# termopar.net
KiCad netlist of a schematic drawn in EAGLE
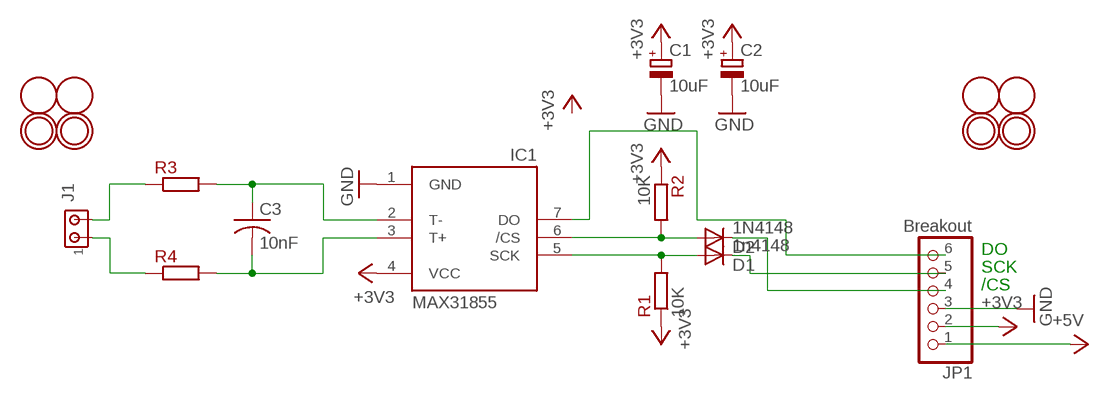
[diagram p0: schematic, sheet 1]

(export (version "E")
  (design (tool "Eeschema 10.0.6"))
  (components
    (comp (ref "C1")
      (value "10uF")
      (footprint "eagle-import:E3,5-8")
      (libsource (lib "eagle-import") (part "CPOL-EUE3.5-8"))
    )
    (comp (ref "C2")
      (value "10uF")
      (footprint "eagle-import:E3,5-8")
      (libsource (lib "eagle-import") (part "CPOL-EUE3.5-8"))
    )
    (comp (ref "C3")
      (value "10nF")
      (footprint "eagle-import:C050-030X075")
      (libsource (lib "eagle-import") (part "C-US050-030X075"))
    )
    (comp (ref "D1")
      (value "1n4148")
      (footprint "eagle-import:DO35-7")
      (libsource (lib "eagle-import") (part "1N4148DO35-7"))
    )
    (comp (ref "D2")
      (value "1N4148")
      (footprint "eagle-import:DO35-7")
      (libsource (lib "eagle-import") (part "1N4148DO35-7"))
    )
    (comp (ref "IC1")
      (value "MAX31855")
      (footprint "eagle-import:SO08")
      (libsource (lib "eagle-import") (part "MAX6675"))
    )
    (comp (ref "J1")
      (value "MTA02-156")
      (footprint "eagle-import:1X2MTA")
      (libsource (lib "eagle-import") (part "MTA02-156"))
    )
    (comp (ref "JP1")
      (value "Breakout")
      (footprint "eagle-import:1X06_ROUND_76")
      (libsource (lib "eagle-import") (part "HEADER-1X676MIL"))
    )
    (comp (ref "R1")
      (value "10K")
      (footprint "eagle-import:0207_10")
      (libsource (lib "eagle-import") (part "R-EU_0207/10"))
    )
    (comp (ref "R2")
      (value "10K")
      (footprint "eagle-import:0207_10")
      (libsource (lib "eagle-import") (part "R-EU_0207/10"))
    )
    (comp (ref "R3")
      (value "R-EU_0204/5")
      (footprint "eagle-import:0204_5")
      (libsource (lib "eagle-import") (part "R-EU_0204/5"))
    )
    (comp (ref "R4")
      (value "R-EU_0204/5")
      (footprint "eagle-import:0204_5")
      (libsource (lib "eagle-import") (part "R-EU_0204/5"))
    )
    (comp (ref "U$1")
      (value "FIDUCIAL")
      (footprint "eagle-import:FIDUCIAL_1MM")
      (libsource (lib "eagle-import") (part "FIDUCIAL"))
    )
    (comp (ref "U$2")
      (value "FIDUCIAL")
      (footprint "eagle-import:FIDUCIAL_1MM")
      (libsource (lib "eagle-import") (part "FIDUCIAL"))
    )
    (comp (ref "U$3")
      (value "FIDUCIAL")
      (footprint "eagle-import:FIDUCIAL_1MM")
      (libsource (lib "eagle-import") (part "FIDUCIAL"))
    )
    (comp (ref "U$4")
      (value "MOUNTINGHOLE2.0")
      (footprint "eagle-import:MOUNTINGHOLE_2.0_PLATED")
      (libsource (lib "eagle-import") (part "MOUNTINGHOLE2.0"))
    )
    (comp (ref "U$5")
      (value "MOUNTINGHOLE2.0")
      (footprint "eagle-import:MOUNTINGHOLE_2.0_PLATED")
      (libsource (lib "eagle-import") (part "MOUNTINGHOLE2.0"))
    )
    (comp (ref "U$6")
      (value "FIDUCIAL")
      (footprint "eagle-import:FIDUCIAL_1MM")
      (libsource (lib "eagle-import") (part "FIDUCIAL"))
    )
    (comp (ref "U$7")
      (value "MOUNTINGHOLE2.0")
      (footprint "eagle-import:MOUNTINGHOLE_2.0_PLATED")
      (libsource (lib "eagle-import") (part "MOUNTINGHOLE2.0"))
    )
    (comp (ref "U$8")
      (value "MOUNTINGHOLE2.0")
      (footprint "eagle-import:MOUNTINGHOLE_2.0_PLATED")
      (libsource (lib "eagle-import") (part "MOUNTINGHOLE2.0"))
    )
  )
  (nets
    (net (code "1") (name "+3V3") (class "Default")
      (node (ref "C1") (pin "+") (pinfunction "+_+") (pintype "passive"))
      (node (ref "C2") (pin "+") (pinfunction "+_+") (pintype "passive"))
      (node (ref "IC1") (pin "4") (pinfunction "VCC_4") (pintype "power_in"))
      (node (ref "JP1") (pin "2") (pinfunction "2_2") (pintype "passive"))
      (node (ref "R1") (pin "1") (pinfunction "1_1") (pintype "passive"))
      (node (ref "R2") (pin "1") (pinfunction "1_1") (pintype "passive"))
    )
    (net (code "2") (name "+5V") (class "Default")
      (node (ref "JP1") (pin "1") (pinfunction "1_1") (pintype "passive"))
    )
    (net (code "3") (name "GND") (class "Default")
      (node (ref "C1") (pin "-") (pinfunction "-_-") (pintype "passive"))
      (node (ref "C2") (pin "-") (pinfunction "-_-") (pintype "passive"))
      (node (ref "IC1") (pin "1") (pinfunction "GND_1") (pintype "power_in"))
      (node (ref "JP1") (pin "3") (pinfunction "3_3") (pintype "passive"))
    )
    (net (code "4") (name "Net-(D1-PadC)") (class "Default")
      (node (ref "D1") (pin "C") (pinfunction "C_C") (pintype "passive"))
      (node (ref "JP1") (pin "5") (pinfunction "5_5") (pintype "passive"))
    )
    (net (code "5") (name "Net-(D2-PadC)") (class "Default")
      (node (ref "D2") (pin "C") (pinfunction "C_C") (pintype "passive"))
      (node (ref "JP1") (pin "4") (pinfunction "4_4") (pintype "passive"))
    )
    (net (code "6") (name "Net-(IC1-DO)") (class "Default")
      (node (ref "IC1") (pin "7") (pinfunction "DO_7") (pintype "output"))
      (node (ref "JP1") (pin "6") (pinfunction "6_6") (pintype "passive"))
    )
    (net (code "7") (name "Net-(IC1-SCK)") (class "Default")
      (node (ref "D1") (pin "A") (pinfunction "A_A") (pintype "passive"))
      (node (ref "IC1") (pin "5") (pinfunction "SCK_5") (pintype "input"))
      (node (ref "R1") (pin "2") (pinfunction "2_2") (pintype "passive"))
    )
    (net (code "8") (name "Net-(IC1-T+)") (class "Default")
      (node (ref "C3") (pin "2") (pinfunction "2_2") (pintype "passive"))
      (node (ref "IC1") (pin "3") (pinfunction "T+_3") (pintype "input"))
      (node (ref "R4") (pin "2") (pinfunction "2_2") (pintype "passive"))
    )
    (net (code "9") (name "Net-(IC1-T-)") (class "Default")
      (node (ref "C3") (pin "1") (pinfunction "1_1") (pintype "passive"))
      (node (ref "IC1") (pin "2") (pinfunction "T-_2") (pintype "input"))
      (node (ref "R3") (pin "2") (pinfunction "2_2") (pintype "passive"))
    )
    (net (code "10") (name "Net-(IC1-{slash}CS)") (class "Default")
      (node (ref "D2") (pin "A") (pinfunction "A_A") (pintype "passive"))
      (node (ref "IC1") (pin "6") (pinfunction "/CS_6") (pintype "input"))
      (node (ref "R2") (pin "2") (pinfunction "2_2") (pintype "passive"))
    )
    (net (code "11") (name "Net-(J1-Pad1)") (class "Default")
      (node (ref "J1") (pin "1") (pinfunction "1_1") (pintype "passive"))
      (node (ref "R4") (pin "1") (pinfunction "1_1") (pintype "passive"))
    )
    (net (code "12") (name "Net-(J1-Pad2)") (class "Default")
      (node (ref "J1") (pin "2") (pinfunction "2_2") (pintype "passive"))
      (node (ref "R3") (pin "1") (pinfunction "1_1") (pintype "passive"))
    )
  )
)
